# Schematic.net
KiCad netlist of a schematic drawn in EAGLE
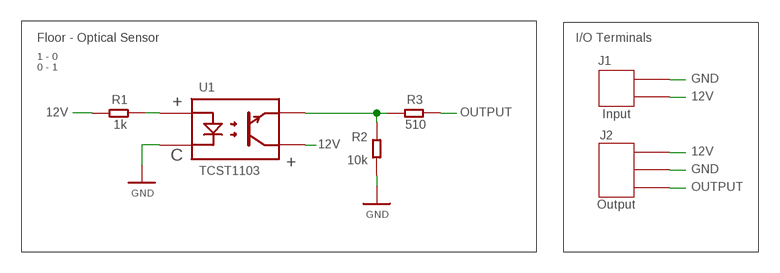
[diagram p0: schematic, sheet 1]

(export (version "E")
  (design (tool "Eeschema 10.0.6"))
  (components
    (comp (ref "J1")
      (value "WF-2R")
      (footprint "eagle-import:WF-2R")
      (libsource (lib "eagle-import") (part "WF-2R"))
    )
    (comp (ref "J2")
      (value "WF-3R")
      (footprint "eagle-import:WF-3R")
      (libsource (lib "eagle-import") (part "WF-3R"))
    )
    (comp (ref "R1")
      (value "1k")
      (footprint "eagle-import:SMD-RES-0603")
      (libsource (lib "eagle-import") (part "SMD-RES-0603"))
    )
    (comp (ref "R2")
      (value "10k")
      (footprint "eagle-import:SMD-RES-0603")
      (libsource (lib "eagle-import") (part "SMD-RES-0603"))
    )
    (comp (ref "R3")
      (value "510")
      (footprint "eagle-import:SMD-RES-0603")
      (libsource (lib "eagle-import") (part "SMD-RES-0603"))
    )
    (comp (ref "U1")
      (value "TCST1103")
      (footprint "eagle-import:TCST1103")
      (libsource (lib "eagle-import") (part "TCST1103"))
    )
  )
  (nets
    (net (code "1") (name "/12V") (class "Default")
      (node (ref "J1") (pin "P$1") (pinfunction "P$1_P$1") (pintype "bidirectional"))
      (node (ref "J2") (pin "P$3") (pinfunction "P$3_P$3") (pintype "bidirectional"))
      (node (ref "R1") (pin "2") (pinfunction "2_2") (pintype "passive"))
      (node (ref "U1") (pin "OUTPUT_VCC") (pinfunction "OUTPUT_VCC_OUTPUT_VCC") (pintype "bidirectional"))
    )
    (net (code "2") (name "/OUTPUT") (class "Default")
      (node (ref "J2") (pin "P$1") (pinfunction "P$1_P$1") (pintype "bidirectional"))
      (node (ref "R3") (pin "1") (pinfunction "1_1") (pintype "passive"))
    )
    (net (code "3") (name "GND") (class "Default")
      (node (ref "J1") (pin "P$2") (pinfunction "P$2_P$2") (pintype "bidirectional"))
      (node (ref "J2") (pin "P$2") (pinfunction "P$2_P$2") (pintype "bidirectional"))
      (node (ref "R2") (pin "2") (pinfunction "2_2") (pintype "passive"))
      (node (ref "U1") (pin "INPUT_C") (pinfunction "C_INPUT_C") (pintype "bidirectional"))
    )
    (net (code "4") (name "Net-(R1-Pad1)") (class "Default")
      (node (ref "R1") (pin "1") (pinfunction "1_1") (pintype "passive"))
      (node (ref "U1") (pin "INPUT_VCC") (pinfunction "INPUT_VCC_INPUT_VCC") (pintype "bidirectional"))
    )
    (net (code "5") (name "Net-(R2-Pad1)") (class "Default")
      (node (ref "R2") (pin "1") (pinfunction "1_1") (pintype "passive"))
      (node (ref "R3") (pin "2") (pinfunction "2_2") (pintype "passive"))
      (node (ref "U1") (pin "OUTPUT") (pinfunction "OUTPUT_OUTPUT") (pintype "bidirectional"))
    )
  )
)
